# poe-light.net
KiCad netlist of a schematic drawn in EAGLE
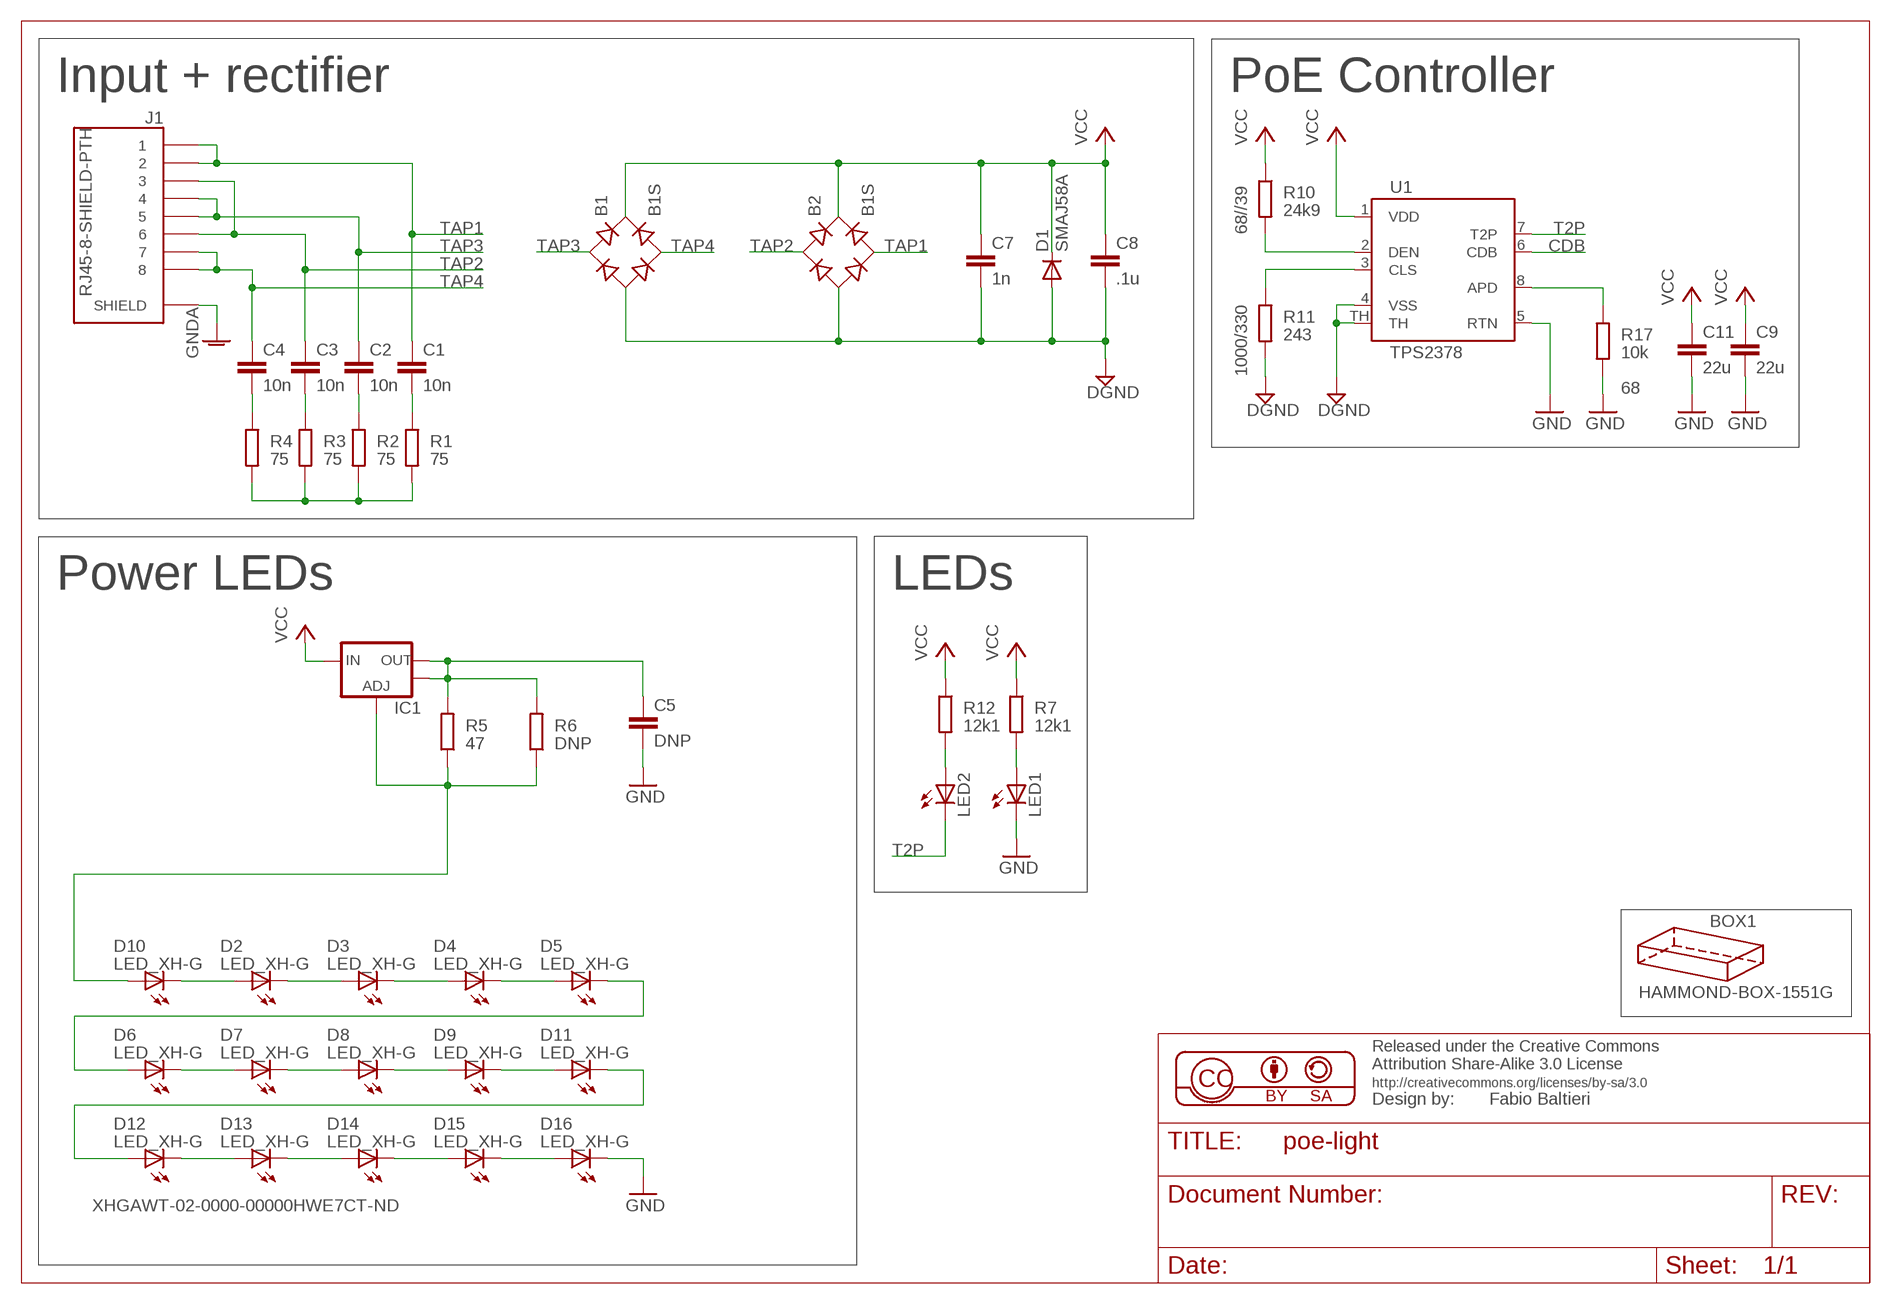
[diagram p0: schematic, sheet 1]

(export (version "E")
  (design (tool "Eeschema 10.0.6"))
  (components
    (comp (ref "B1")
      (value "B1S")
      (footprint "eagle-import:MBS")
      (libsource (lib "eagle-import") (part "BS1"))
    )
    (comp (ref "B2")
      (value "B1S")
      (footprint "eagle-import:MBS")
      (libsource (lib "eagle-import") (part "BS1"))
    )
    (comp (ref "BOX1")
      (value "HAMMOND-BOX-1551G")
      (footprint "eagle-import:1551G")
      (libsource (lib "eagle-import") (part "HAMMOND-BOX-1551G"))
    )
    (comp (ref "C1")
      (value "10n")
      (footprint "eagle-import:C0603")
      (libsource (lib "eagle-import") (part "C-EUC0603"))
    )
    (comp (ref "C2")
      (value "10n")
      (footprint "eagle-import:C0603")
      (libsource (lib "eagle-import") (part "C-EUC0603"))
    )
    (comp (ref "C3")
      (value "10n")
      (footprint "eagle-import:C0603")
      (libsource (lib "eagle-import") (part "C-EUC0603"))
    )
    (comp (ref "C4")
      (value "10n")
      (footprint "eagle-import:C0603")
      (libsource (lib "eagle-import") (part "C-EUC0603"))
    )
    (comp (ref "C5")
      (value "DNP")
      (footprint "eagle-import:C0805")
      (libsource (lib "eagle-import") (part "C-EUC0805"))
    )
    (comp (ref "C7")
      (value "1n")
      (footprint "eagle-import:C0603")
      (libsource (lib "eagle-import") (part "C-EUC0603"))
    )
    (comp (ref "C8")
      (value ".1u")
      (footprint "eagle-import:C0603")
      (libsource (lib "eagle-import") (part "C-EUC0603"))
    )
    (comp (ref "C9")
      (value "22u")
      (footprint "eagle-import:C1206")
      (libsource (lib "eagle-import") (part "C-EUC1206"))
    )
    (comp (ref "C11")
      (value "22u")
      (footprint "eagle-import:C1206")
      (libsource (lib "eagle-import") (part "C-EUC1206"))
    )
    (comp (ref "D1")
      (value "SMAJ58A")
      (footprint "eagle-import:SMA-DIODE")
      (libsource (lib "eagle-import") (part "DIODESMA"))
    )
    (comp (ref "D2")
      (value "LED_XH-G")
      (footprint "eagle-import:CREE_XHG")
      (libsource (lib "eagle-import") (part "LED_XH-G"))
    )
    (comp (ref "D3")
      (value "LED_XH-G")
      (footprint "eagle-import:CREE_XHG")
      (libsource (lib "eagle-import") (part "LED_XH-G"))
    )
    (comp (ref "D4")
      (value "LED_XH-G")
      (footprint "eagle-import:CREE_XHG")
      (libsource (lib "eagle-import") (part "LED_XH-G"))
    )
    (comp (ref "D5")
      (value "LED_XH-G")
      (footprint "eagle-import:CREE_XHG")
      (libsource (lib "eagle-import") (part "LED_XH-G"))
    )
    (comp (ref "D6")
      (value "LED_XH-G")
      (footprint "eagle-import:CREE_XHG")
      (libsource (lib "eagle-import") (part "LED_XH-G"))
    )
    (comp (ref "D7")
      (value "LED_XH-G")
      (footprint "eagle-import:CREE_XHG")
      (libsource (lib "eagle-import") (part "LED_XH-G"))
    )
    (comp (ref "D8")
      (value "LED_XH-G")
      (footprint "eagle-import:CREE_XHG")
      (libsource (lib "eagle-import") (part "LED_XH-G"))
    )
    (comp (ref "D9")
      (value "LED_XH-G")
      (footprint "eagle-import:CREE_XHG")
      (libsource (lib "eagle-import") (part "LED_XH-G"))
    )
    (comp (ref "D10")
      (value "LED_XH-G")
      (footprint "eagle-import:CREE_XHG")
      (libsource (lib "eagle-import") (part "LED_XH-G"))
    )
    (comp (ref "D11")
      (value "LED_XH-G")
      (footprint "eagle-import:CREE_XHG")
      (libsource (lib "eagle-import") (part "LED_XH-G"))
    )
    (comp (ref "D12")
      (value "LED_XH-G")
      (footprint "eagle-import:CREE_XHG")
      (libsource (lib "eagle-import") (part "LED_XH-G"))
    )
    (comp (ref "D13")
      (value "LED_XH-G")
      (footprint "eagle-import:CREE_XHG")
      (libsource (lib "eagle-import") (part "LED_XH-G"))
    )
    (comp (ref "D14")
      (value "LED_XH-G")
      (footprint "eagle-import:CREE_XHG")
      (libsource (lib "eagle-import") (part "LED_XH-G"))
    )
    (comp (ref "D15")
      (value "LED_XH-G")
      (footprint "eagle-import:CREE_XHG")
      (libsource (lib "eagle-import") (part "LED_XH-G"))
    )
    (comp (ref "D16")
      (value "LED_XH-G")
      (footprint "eagle-import:CREE_XHG")
      (libsource (lib "eagle-import") (part "LED_XH-G"))
    )
    (comp (ref "IC1")
      (value "V_REG_LM1117SOT223")
      (footprint "eagle-import:SOT223")
      (libsource (lib "eagle-import") (part "V_REG_LM1117SOT223"))
    )
    (comp (ref "J1")
      (value "RJ45-8-SHIELD-PTH")
      (footprint "eagle-import:RJ45-8-SHIELD")
      (libsource (lib "eagle-import") (part "RJ45-8-SHIELD-PTH"))
    )
    (comp (ref "LED1")
      (value "LEDSML0805")
      (footprint "eagle-import:SML0805")
      (libsource (lib "eagle-import") (part "LEDSML0805"))
    )
    (comp (ref "LED2")
      (value "LEDSML0805")
      (footprint "eagle-import:SML0805")
      (libsource (lib "eagle-import") (part "LEDSML0805"))
    )
    (comp (ref "R1")
      (value "75")
      (footprint "eagle-import:R0603")
      (libsource (lib "eagle-import") (part "R-EU_R0603"))
    )
    (comp (ref "R2")
      (value "75")
      (footprint "eagle-import:R0603")
      (libsource (lib "eagle-import") (part "R-EU_R0603"))
    )
    (comp (ref "R3")
      (value "75")
      (footprint "eagle-import:R0603")
      (libsource (lib "eagle-import") (part "R-EU_R0603"))
    )
    (comp (ref "R4")
      (value "75")
      (footprint "eagle-import:R0603")
      (libsource (lib "eagle-import") (part "R-EU_R0603"))
    )
    (comp (ref "R5")
      (value "47")
      (footprint "eagle-import:R1206")
      (libsource (lib "eagle-import") (part "R-EU_R1206"))
    )
    (comp (ref "R6")
      (value "DNP")
      (footprint "eagle-import:R1206")
      (libsource (lib "eagle-import") (part "R-EU_R1206"))
    )
    (comp (ref "R7")
      (value "12k1")
      (footprint "eagle-import:R0603")
      (libsource (lib "eagle-import") (part "R-EU_R0603"))
    )
    (comp (ref "R10")
      (value "24k9")
      (footprint "eagle-import:R0603")
      (libsource (lib "eagle-import") (part "R-EU_R0603"))
    )
    (comp (ref "R11")
      (value "243")
      (footprint "eagle-import:R0603")
      (libsource (lib "eagle-import") (part "R-EU_R0603"))
    )
    (comp (ref "R12")
      (value "12k1")
      (footprint "eagle-import:R0603")
      (libsource (lib "eagle-import") (part "R-EU_R0603"))
    )
    (comp (ref "R17")
      (value "10k")
      (footprint "eagle-import:R0603")
      (libsource (lib "eagle-import") (part "R-EU_R0603"))
    )
    (comp (ref "U1")
      (value "TPS2378")
      (footprint "eagle-import:SOIC8-POWERPAD")
      (libsource (lib "eagle-import") (part "TPS2378"))
    )
  )
  (nets
    (net (code "1") (name "/CDB") (class "Default")
      (node (ref "U1") (pin "6") (pinfunction "CDB_6") (pintype "bidirectional"))
    )
    (net (code "2") (name "/T2P") (class "Default")
      (node (ref "LED2") (pin "C") (pinfunction "C_C") (pintype "passive"))
      (node (ref "U1") (pin "7") (pinfunction "T2P_7") (pintype "bidirectional"))
    )
    (net (code "3") (name "/TAP1") (class "Default")
      (node (ref "B2") (pin "AC2") (pinfunction "AC2_AC2") (pintype "passive"))
      (node (ref "C1") (pin "1") (pinfunction "1_1") (pintype "passive"))
      (node (ref "J1") (pin "1") (pinfunction "1_1") (pintype "bidirectional"))
      (node (ref "J1") (pin "2") (pinfunction "2_2") (pintype "bidirectional"))
    )
    (net (code "4") (name "/TAP2") (class "Default")
      (node (ref "B2") (pin "AC1") (pinfunction "AC1_AC1") (pintype "passive"))
      (node (ref "C3") (pin "1") (pinfunction "1_1") (pintype "passive"))
      (node (ref "J1") (pin "3") (pinfunction "3_3") (pintype "bidirectional"))
      (node (ref "J1") (pin "6") (pinfunction "6_6") (pintype "bidirectional"))
    )
    (net (code "5") (name "/TAP3") (class "Default")
      (node (ref "B1") (pin "AC1") (pinfunction "AC1_AC1") (pintype "passive"))
      (node (ref "C2") (pin "1") (pinfunction "1_1") (pintype "passive"))
      (node (ref "J1") (pin "4") (pinfunction "4_4") (pintype "bidirectional"))
      (node (ref "J1") (pin "5") (pinfunction "5_5") (pintype "bidirectional"))
    )
    (net (code "6") (name "/TAP4") (class "Default")
      (node (ref "B1") (pin "AC2") (pinfunction "AC2_AC2") (pintype "passive"))
      (node (ref "C4") (pin "1") (pinfunction "1_1") (pintype "passive"))
      (node (ref "J1") (pin "7") (pinfunction "7_7") (pintype "bidirectional"))
      (node (ref "J1") (pin "8") (pinfunction "8_8") (pintype "bidirectional"))
    )
    (net (code "7") (name "DGND") (class "Default")
      (node (ref "B1") (pin "-") (pinfunction "-_-") (pintype "passive"))
      (node (ref "B2") (pin "-") (pinfunction "-_-") (pintype "passive"))
      (node (ref "C7") (pin "2") (pinfunction "2_2") (pintype "passive"))
      (node (ref "C8") (pin "2") (pinfunction "2_2") (pintype "passive"))
      (node (ref "D1") (pin "A") (pinfunction "A_A") (pintype "passive"))
      (node (ref "R11") (pin "2") (pinfunction "2_2") (pintype "passive"))
      (node (ref "U1") (pin "4") (pinfunction "VSS_4") (pintype "bidirectional"))
      (node (ref "U1") (pin "TH") (pinfunction "TH_TH") (pintype "bidirectional"))
    )
    (net (code "8") (name "GND") (class "Default")
      (node (ref "C11") (pin "2") (pinfunction "2_2") (pintype "passive"))
      (node (ref "C5") (pin "2") (pinfunction "2_2") (pintype "passive"))
      (node (ref "C9") (pin "2") (pinfunction "2_2") (pintype "passive"))
      (node (ref "D16") (pin "C") (pinfunction "C_C") (pintype "passive"))
      (node (ref "D16") (pin "C@1") (pinfunction "C_C@1") (pintype "passive"))
      (node (ref "LED1") (pin "C") (pinfunction "C_C") (pintype "passive"))
      (node (ref "R17") (pin "2") (pinfunction "2_2") (pintype "passive"))
      (node (ref "U1") (pin "5") (pinfunction "RTN_5") (pintype "bidirectional"))
    )
    (net (code "9") (name "GNDA") (class "Default")
      (node (ref "J1") (pin "P$1") (pinfunction "SHIELD_P$1") (pintype "bidirectional"))
      (node (ref "J1") (pin "P$2") (pinfunction "SHIELD_P$2") (pintype "bidirectional"))
    )
    (net (code "10") (name "Net-(C1-Pad2)") (class "Default")
      (node (ref "C1") (pin "2") (pinfunction "2_2") (pintype "passive"))
      (node (ref "R1") (pin "1") (pinfunction "1_1") (pintype "passive"))
    )
    (net (code "11") (name "Net-(C2-Pad2)") (class "Default")
      (node (ref "C2") (pin "2") (pinfunction "2_2") (pintype "passive"))
      (node (ref "R2") (pin "1") (pinfunction "1_1") (pintype "passive"))
    )
    (net (code "12") (name "Net-(C3-Pad2)") (class "Default")
      (node (ref "C3") (pin "2") (pinfunction "2_2") (pintype "passive"))
      (node (ref "R3") (pin "1") (pinfunction "1_1") (pintype "passive"))
    )
    (net (code "13") (name "Net-(C4-Pad2)") (class "Default")
      (node (ref "C4") (pin "2") (pinfunction "2_2") (pintype "passive"))
      (node (ref "R4") (pin "1") (pinfunction "1_1") (pintype "passive"))
    )
    (net (code "14") (name "Net-(C5-Pad1)") (class "Default")
      (node (ref "C5") (pin "1") (pinfunction "1_1") (pintype "passive"))
      (node (ref "IC1") (pin "2") (pinfunction "OUT_2") (pintype "output"))
      (node (ref "IC1") (pin "4") (pinfunction "OUT_4") (pintype "output"))
      (node (ref "R5") (pin "2") (pinfunction "2_2") (pintype "passive"))
      (node (ref "R6") (pin "2") (pinfunction "2_2") (pintype "passive"))
    )
    (net (code "15") (name "Net-(D2-C-PadC@1)") (class "Default")
      (node (ref "D2") (pin "C") (pinfunction "C_C") (pintype "passive"))
      (node (ref "D2") (pin "C@1") (pinfunction "C_C@1") (pintype "passive"))
      (node (ref "D3") (pin "A") (pinfunction "A_A") (pintype "passive"))
      (node (ref "D3") (pin "A@1") (pinfunction "A_A@1") (pintype "passive"))
    )
    (net (code "16") (name "Net-(D3-C-PadC@1)") (class "Default")
      (node (ref "D3") (pin "C") (pinfunction "C_C") (pintype "passive"))
      (node (ref "D3") (pin "C@1") (pinfunction "C_C@1") (pintype "passive"))
      (node (ref "D4") (pin "A") (pinfunction "A_A") (pintype "passive"))
      (node (ref "D4") (pin "A@1") (pinfunction "A_A@1") (pintype "passive"))
    )
    (net (code "17") (name "Net-(D4-C-PadC@1)") (class "Default")
      (node (ref "D4") (pin "C") (pinfunction "C_C") (pintype "passive"))
      (node (ref "D4") (pin "C@1") (pinfunction "C_C@1") (pintype "passive"))
      (node (ref "D5") (pin "A") (pinfunction "A_A") (pintype "passive"))
      (node (ref "D5") (pin "A@1") (pinfunction "A_A@1") (pintype "passive"))
    )
    (net (code "18") (name "Net-(D5-C-PadC@1)") (class "Default")
      (node (ref "D5") (pin "C") (pinfunction "C_C") (pintype "passive"))
      (node (ref "D5") (pin "C@1") (pinfunction "C_C@1") (pintype "passive"))
      (node (ref "D6") (pin "A") (pinfunction "A_A") (pintype "passive"))
      (node (ref "D6") (pin "A@1") (pinfunction "A_A@1") (pintype "passive"))
    )
    (net (code "19") (name "Net-(D6-C-PadC@1)") (class "Default")
      (node (ref "D6") (pin "C") (pinfunction "C_C") (pintype "passive"))
      (node (ref "D6") (pin "C@1") (pinfunction "C_C@1") (pintype "passive"))
      (node (ref "D7") (pin "A") (pinfunction "A_A") (pintype "passive"))
      (node (ref "D7") (pin "A@1") (pinfunction "A_A@1") (pintype "passive"))
    )
    (net (code "20") (name "Net-(D7-C-PadC@1)") (class "Default")
      (node (ref "D7") (pin "C") (pinfunction "C_C") (pintype "passive"))
      (node (ref "D7") (pin "C@1") (pinfunction "C_C@1") (pintype "passive"))
      (node (ref "D8") (pin "A") (pinfunction "A_A") (pintype "passive"))
      (node (ref "D8") (pin "A@1") (pinfunction "A_A@1") (pintype "passive"))
    )
    (net (code "21") (name "Net-(D8-C-PadC@1)") (class "Default")
      (node (ref "D8") (pin "C") (pinfunction "C_C") (pintype "passive"))
      (node (ref "D8") (pin "C@1") (pinfunction "C_C@1") (pintype "passive"))
      (node (ref "D9") (pin "A") (pinfunction "A_A") (pintype "passive"))
      (node (ref "D9") (pin "A@1") (pinfunction "A_A@1") (pintype "passive"))
    )
    (net (code "22") (name "Net-(D10-C-PadC@1)") (class "Default")
      (node (ref "D10") (pin "C") (pinfunction "C_C") (pintype "passive"))
      (node (ref "D10") (pin "C@1") (pinfunction "C_C@1") (pintype "passive"))
      (node (ref "D2") (pin "A") (pinfunction "A_A") (pintype "passive"))
      (node (ref "D2") (pin "A@1") (pinfunction "A_A@1") (pintype "passive"))
    )
    (net (code "23") (name "Net-(D11-A-PadA@1)") (class "Default")
      (node (ref "D11") (pin "A") (pinfunction "A_A") (pintype "passive"))
      (node (ref "D11") (pin "A@1") (pinfunction "A_A@1") (pintype "passive"))
      (node (ref "D9") (pin "C") (pinfunction "C_C") (pintype "passive"))
      (node (ref "D9") (pin "C@1") (pinfunction "C_C@1") (pintype "passive"))
    )
    (net (code "24") (name "Net-(D11-C-PadC@1)") (class "Default")
      (node (ref "D11") (pin "C") (pinfunction "C_C") (pintype "passive"))
      (node (ref "D11") (pin "C@1") (pinfunction "C_C@1") (pintype "passive"))
      (node (ref "D12") (pin "A") (pinfunction "A_A") (pintype "passive"))
      (node (ref "D12") (pin "A@1") (pinfunction "A_A@1") (pintype "passive"))
    )
    (net (code "25") (name "Net-(D12-C-PadC@1)") (class "Default")
      (node (ref "D12") (pin "C") (pinfunction "C_C") (pintype "passive"))
      (node (ref "D12") (pin "C@1") (pinfunction "C_C@1") (pintype "passive"))
      (node (ref "D13") (pin "A") (pinfunction "A_A") (pintype "passive"))
      (node (ref "D13") (pin "A@1") (pinfunction "A_A@1") (pintype "passive"))
    )
    (net (code "26") (name "Net-(D13-C-PadC@1)") (class "Default")
      (node (ref "D13") (pin "C") (pinfunction "C_C") (pintype "passive"))
      (node (ref "D13") (pin "C@1") (pinfunction "C_C@1") (pintype "passive"))
      (node (ref "D14") (pin "A") (pinfunction "A_A") (pintype "passive"))
      (node (ref "D14") (pin "A@1") (pinfunction "A_A@1") (pintype "passive"))
    )
    (net (code "27") (name "Net-(D14-C-PadC@1)") (class "Default")
      (node (ref "D14") (pin "C") (pinfunction "C_C") (pintype "passive"))
      (node (ref "D14") (pin "C@1") (pinfunction "C_C@1") (pintype "passive"))
      (node (ref "D15") (pin "A") (pinfunction "A_A") (pintype "passive"))
      (node (ref "D15") (pin "A@1") (pinfunction "A_A@1") (pintype "passive"))
    )
    (net (code "28") (name "Net-(D15-C-PadC@1)") (class "Default")
      (node (ref "D15") (pin "C") (pinfunction "C_C") (pintype "passive"))
      (node (ref "D15") (pin "C@1") (pinfunction "C_C@1") (pintype "passive"))
      (node (ref "D16") (pin "A") (pinfunction "A_A") (pintype "passive"))
      (node (ref "D16") (pin "A@1") (pinfunction "A_A@1") (pintype "passive"))
    )
    (net (code "29") (name "Net-(IC1-ADJ)") (class "Default")
      (node (ref "D10") (pin "A") (pinfunction "A_A") (pintype "passive"))
      (node (ref "D10") (pin "A@1") (pinfunction "A_A@1") (pintype "passive"))
      (node (ref "IC1") (pin "1") (pinfunction "ADJ_1") (pintype "input"))
      (node (ref "R5") (pin "1") (pinfunction "1_1") (pintype "passive"))
      (node (ref "R6") (pin "1") (pinfunction "1_1") (pintype "passive"))
    )
    (net (code "30") (name "Net-(LED1-PadA)") (class "Default")
      (node (ref "LED1") (pin "A") (pinfunction "A_A") (pintype "passive"))
      (node (ref "R7") (pin "2") (pinfunction "2_2") (pintype "passive"))
    )
    (net (code "31") (name "Net-(LED2-PadA)") (class "Default")
      (node (ref "LED2") (pin "A") (pinfunction "A_A") (pintype "passive"))
      (node (ref "R12") (pin "2") (pinfunction "2_2") (pintype "passive"))
    )
    (net (code "32") (name "Net-(R1-Pad2)") (class "Default")
      (node (ref "R1") (pin "2") (pinfunction "2_2") (pintype "passive"))
      (node (ref "R2") (pin "2") (pinfunction "2_2") (pintype "passive"))
      (node (ref "R3") (pin "2") (pinfunction "2_2") (pintype "passive"))
      (node (ref "R4") (pin "2") (pinfunction "2_2") (pintype "passive"))
    )
    (net (code "33") (name "Net-(U1-APD)") (class "Default")
      (node (ref "R17") (pin "1") (pinfunction "1_1") (pintype "passive"))
      (node (ref "U1") (pin "8") (pinfunction "APD_8") (pintype "bidirectional"))
    )
    (net (code "34") (name "Net-(U1-CLS)") (class "Default")
      (node (ref "R11") (pin "1") (pinfunction "1_1") (pintype "passive"))
      (node (ref "U1") (pin "3") (pinfunction "CLS_3") (pintype "bidirectional"))
    )
    (net (code "35") (name "Net-(U1-DEN)") (class "Default")
      (node (ref "R10") (pin "2") (pinfunction "2_2") (pintype "passive"))
      (node (ref "U1") (pin "2") (pinfunction "DEN_2") (pintype "bidirectional"))
    )
    (net (code "36") (name "VCC") (class "Default")
      (node (ref "B1") (pin "+") (pinfunction "+_+") (pintype "passive"))
      (node (ref "B2") (pin "+") (pinfunction "+_+") (pintype "passive"))
      (node (ref "C11") (pin "1") (pinfunction "1_1") (pintype "passive"))
      (node (ref "C7") (pin "1") (pinfunction "1_1") (pintype "passive"))
      (node (ref "C8") (pin "1") (pinfunction "1_1") (pintype "passive"))
      (node (ref "C9") (pin "1") (pinfunction "1_1") (pintype "passive"))
      (node (ref "D1") (pin "C") (pinfunction "C_C") (pintype "passive"))
      (node (ref "IC1") (pin "3") (pinfunction "IN_3") (pintype "input"))
      (node (ref "R10") (pin "1") (pinfunction "1_1") (pintype "passive"))
      (node (ref "R12") (pin "1") (pinfunction "1_1") (pintype "passive"))
      (node (ref "R7") (pin "1") (pinfunction "1_1") (pintype "passive"))
      (node (ref "U1") (pin "1") (pinfunction "VDD_1") (pintype "bidirectional"))
    )
  )
)
